# slush_cap_board_rev_c.net
KiCad netlist of a schematic drawn in EAGLE
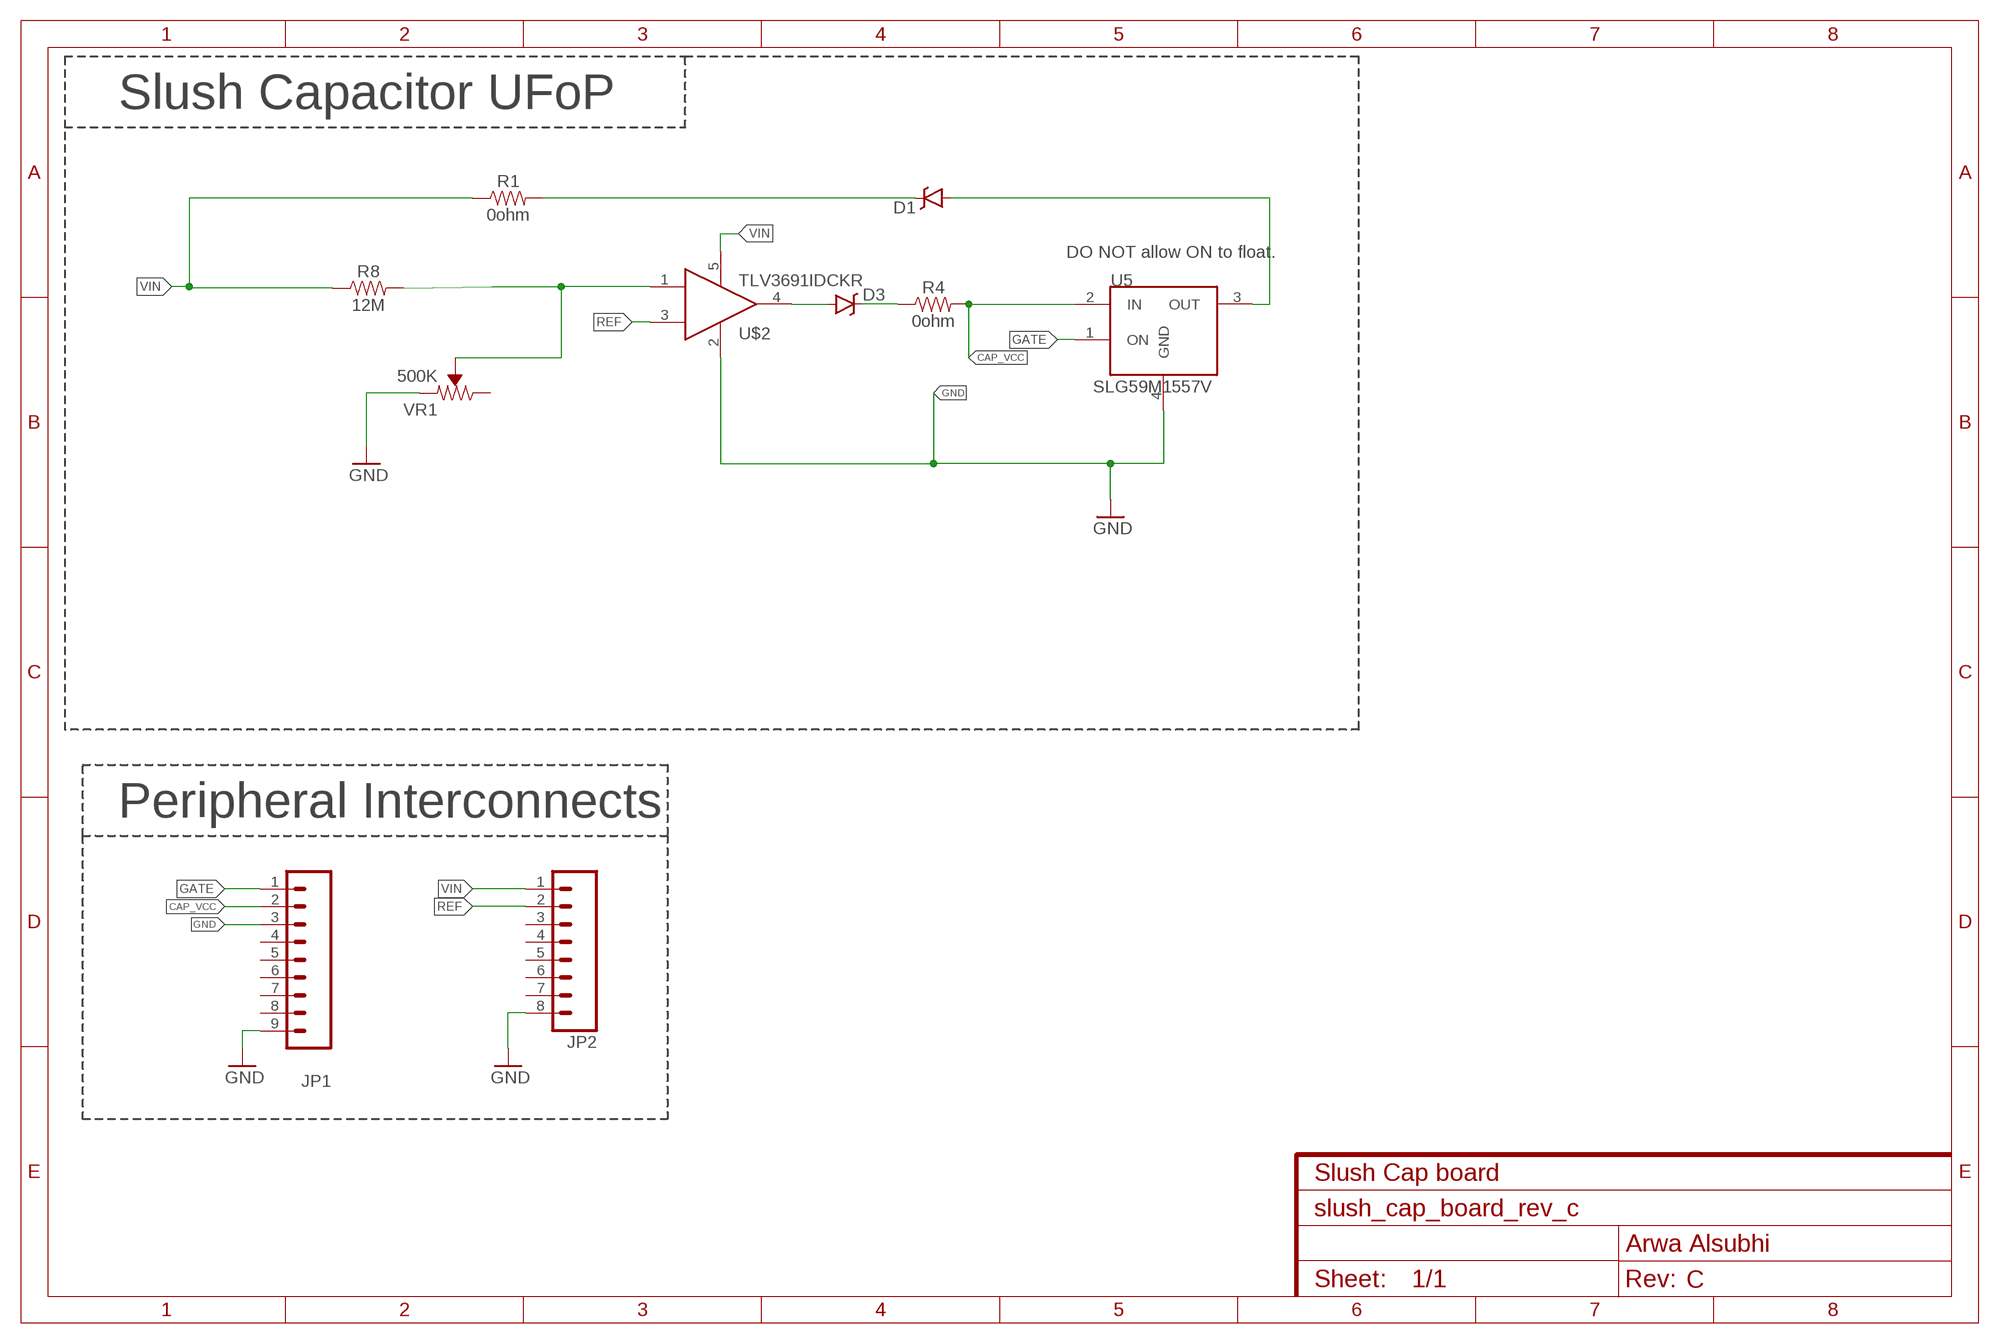
[diagram p0: schematic, sheet 1]

(export (version "E")
  (design (tool "Eeschema 10.0.6"))
  (components
    (comp (ref "D1")
      (value "RB751")
      (footprint "eagle-import:SOD-523")
      (fields (field (name "MPN") "BAS40-02V-V-G-08"))
      (libsource (lib "eagle-import") (part "DIODE-SCHOTTKY-RB751"))
    )
    (comp (ref "D3")
      (value "RB751")
      (footprint "eagle-import:SOD-523")
      (fields (field (name "MPN") "BAS40-02V-V-G-08"))
      (libsource (lib "eagle-import") (part "DIODE-SCHOTTKY-RB751"))
    )
    (comp (ref "JP1")
      (value "M091.27MM")
      (footprint "eagle-import:1X09-1.27MM")
      (fields (field (name "MANUFACTURERPARTNUMBER") "GRPB091VWVN-RC ") (field (name "MPN") "GRPB091VWVN-RC"))
      (libsource (lib "eagle-import") (part "M091.27MM"))
    )
    (comp (ref "JP2")
      (value "M081.27MM")
      (footprint "eagle-import:1X08-1.27MM")
      (fields (field (name "MANUFACTURERPARTNUMBER") "GRPB081VWVN-RC "))
      (libsource (lib "eagle-import") (part "M081.27MM"))
    )
    (comp (ref "R1")
      (value "0ohm")
      (footprint "eagle-import:0603")
      (libsource (lib "eagle-import") (part "0603-RESISTOR-0603-1/10W-1%"))
    )
    (comp (ref "R4")
      (value "0ohm")
      (footprint "eagle-import:0603")
      (libsource (lib "eagle-import") (part "0603-RESISTOR-0603-1/10W-1%"))
    )
    (comp (ref "R8")
      (value "12M")
      (footprint "eagle-import:0805")
      (libsource (lib "eagle-import") (part "0.3OHM-0805-1/8W-1%"))
    )
    (comp (ref "U$2")
      (value "TLV3691IDCKR")
      (footprint "eagle-import:SOT353")
      (libsource (lib "eagle-import") (part "TLV3691IDCKR"))
    )
    (comp (ref "U5")
      (value "SLG59M1557V")
      (footprint "eagle-import:4STDFN")
      (fields (field (name "MPN") "SLG59M1557V "))
      (libsource (lib "eagle-import") (part "SLG59M1557V"))
    )
    (comp (ref "VR1")
      (value "500K")
      (footprint "eagle-import:TRIMPOT-SMD-3MM-CLOSED")
      (libsource (lib "eagle-import") (part "TRIMPOT-SMD-3MM-CLOSED-1/8W-20%"))
    )
  )
  (nets
    (net (code "1") (name "CAP_VCC") (class "Default")
      (node (ref "JP1") (pin "2") (pinfunction "2_2") (pintype "passive"))
      (node (ref "R4") (pin "2") (pinfunction "2_2") (pintype "passive"))
      (node (ref "U5") (pin "2") (pinfunction "IN_2") (pintype "bidirectional"))
    )
    (net (code "2") (name "GATE") (class "Default")
      (node (ref "JP1") (pin "1") (pinfunction "1_1") (pintype "passive"))
      (node (ref "U5") (pin "1") (pinfunction "ON_1") (pintype "bidirectional"))
    )
    (net (code "3") (name "GND") (class "Default")
      (node (ref "JP1") (pin "3") (pinfunction "3_3") (pintype "passive"))
      (node (ref "JP1") (pin "9") (pinfunction "9_9") (pintype "passive"))
      (node (ref "JP2") (pin "8") (pinfunction "8_8") (pintype "passive"))
      (node (ref "U$2") (pin "2") (pinfunction "2_2") (pintype "bidirectional"))
      (node (ref "U5") (pin "4") (pinfunction "GND_4") (pintype "bidirectional"))
      (node (ref "VR1") (pin "1") (pinfunction "CCW_1") (pintype "passive"))
    )
    (net (code "4") (name "Net-(D1-PadC)") (class "Default")
      (node (ref "D1") (pin "C") (pinfunction "C_C") (pintype "passive"))
      (node (ref "R1") (pin "2") (pinfunction "2_2") (pintype "passive"))
    )
    (net (code "5") (name "Net-(D3-PadA)") (class "Default")
      (node (ref "D3") (pin "A") (pinfunction "A_A") (pintype "passive"))
      (node (ref "U$2") (pin "4") (pinfunction "4_4") (pintype "bidirectional"))
    )
    (net (code "6") (name "Net-(D3-PadC)") (class "Default")
      (node (ref "D3") (pin "C") (pinfunction "C_C") (pintype "passive"))
      (node (ref "R4") (pin "1") (pinfunction "1_1") (pintype "passive"))
    )
    (net (code "7") (name "Net-(U5-OUT)") (class "Default")
      (node (ref "D1") (pin "A") (pinfunction "A_A") (pintype "passive"))
      (node (ref "U5") (pin "3") (pinfunction "OUT_3") (pintype "bidirectional"))
    )
    (net (code "8") (name "Net-(VR1-WIPER)") (class "Default")
      (node (ref "R8") (pin "2") (pinfunction "2_2") (pintype "passive"))
      (node (ref "U$2") (pin "1") (pinfunction "1_1") (pintype "bidirectional"))
      (node (ref "VR1") (pin "2") (pinfunction "WIPER_2") (pintype "passive"))
    )
    (net (code "9") (name "REF") (class "Default")
      (node (ref "JP2") (pin "2") (pinfunction "2_2") (pintype "passive"))
      (node (ref "U$2") (pin "3") (pinfunction "3_3") (pintype "bidirectional"))
    )
    (net (code "10") (name "VIN") (class "Default")
      (node (ref "JP2") (pin "1") (pinfunction "1_1") (pintype "passive"))
      (node (ref "R1") (pin "1") (pinfunction "1_1") (pintype "passive"))
      (node (ref "R8") (pin "1") (pinfunction "1_1") (pintype "passive"))
      (node (ref "U$2") (pin "5") (pinfunction "5_5") (pintype "bidirectional"))
    )
    (net (code "11") (name "unconnected-(JP1-Pad4)") (class "Default")
      (node (ref "JP1") (pin "4") (pinfunction "4_4") (pintype "passive"))
    )
    (net (code "12") (name "unconnected-(JP1-Pad5)") (class "Default")
      (node (ref "JP1") (pin "5") (pinfunction "5_5") (pintype "passive"))
    )
    (net (code "13") (name "unconnected-(JP1-Pad6)") (class "Default")
      (node (ref "JP1") (pin "6") (pinfunction "6_6") (pintype "passive"))
    )
    (net (code "14") (name "unconnected-(JP1-Pad7)") (class "Default")
      (node (ref "JP1") (pin "7") (pinfunction "7_7") (pintype "passive"))
    )
    (net (code "15") (name "unconnected-(JP1-Pad8)") (class "Default")
      (node (ref "JP1") (pin "8") (pinfunction "8_8") (pintype "passive"))
    )
    (net (code "16") (name "unconnected-(JP2-Pad3)") (class "Default")
      (node (ref "JP2") (pin "3") (pinfunction "3_3") (pintype "passive"))
    )
    (net (code "17") (name "unconnected-(JP2-Pad4)") (class "Default")
      (node (ref "JP2") (pin "4") (pinfunction "4_4") (pintype "passive"))
    )
    (net (code "18") (name "unconnected-(JP2-Pad5)") (class "Default")
      (node (ref "JP2") (pin "5") (pinfunction "5_5") (pintype "passive"))
    )
    (net (code "19") (name "unconnected-(JP2-Pad6)") (class "Default")
      (node (ref "JP2") (pin "6") (pinfunction "6_6") (pintype "passive"))
    )
    (net (code "20") (name "unconnected-(JP2-Pad7)") (class "Default")
      (node (ref "JP2") (pin "7") (pinfunction "7_7") (pintype "passive"))
    )
    (net (code "21") (name "unconnected-(VR1-CW-Pad3)") (class "Default")
      (node (ref "VR1") (pin "3") (pinfunction "CW_3") (pintype "passive"))
    )
  )
)
